# Probe_Schematic.net
KiCad netlist of a schematic drawn in EAGLE
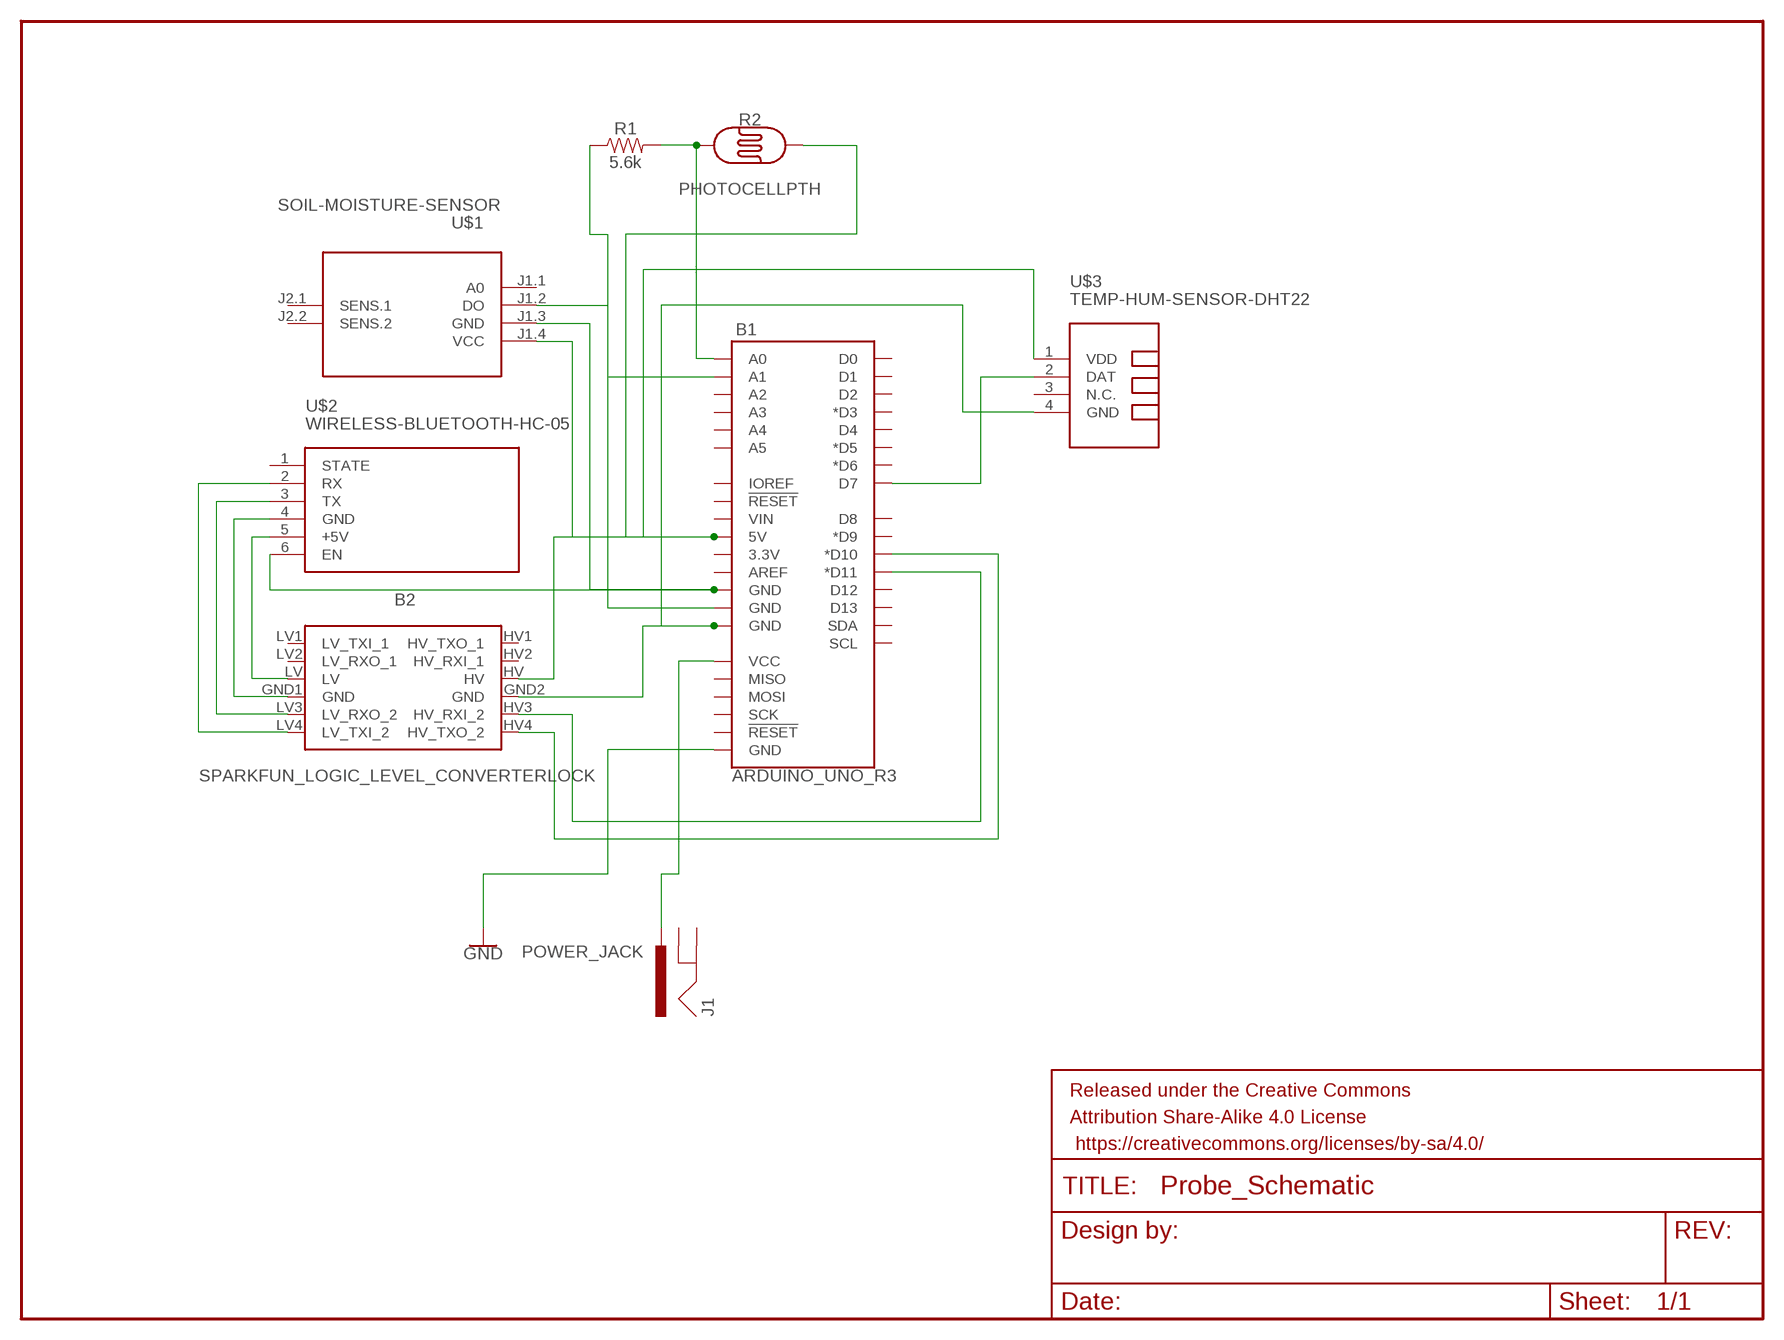
[diagram p0: schematic, sheet 1]

(export (version "E")
  (design (tool "Eeschema 10.0.6"))
  (components
    (comp (ref "B1")
      (value "ARDUINO_UNO_R3")
      (footprint "eagle-import:ARDUINO_R3")
      (libsource (lib "eagle-import") (part "ARDUINO_UNO_R3"))
    )
    (comp (ref "B2")
      (value "SPARKFUN_LOGIC_LEVEL_CONVERTERLOCK")
      (footprint "eagle-import:SPARKFUN_LOGIC_LEVEL_CONVERTER_LOCK")
      (libsource (lib "eagle-import") (part "SPARKFUN_LOGIC_LEVEL_CONVERTERLOCK"))
    )
    (comp (ref "FRAME1")
      (value "FRAME-LETTER")
      (footprint "eagle-import:CREATIVE_COMMONS")
      (libsource (lib "eagle-import") (part "FRAME-LETTER"))
    )
    (comp (ref "J1")
      (value "POWER_JACK")
      (footprint "eagle-import:POWER_JACK_PTH")
      (libsource (lib "eagle-import") (part "POWER_JACK"))
    )
    (comp (ref "R1")
      (value "5.6k")
      (footprint "eagle-import:0603")
      (libsource (lib "eagle-import") (part "5.6KOHM-0603-1/10W-1%"))
    )
    (comp (ref "R2")
      (value "PHOTOCELLPTH")
      (footprint "eagle-import:PHOTOCELL")
      (libsource (lib "eagle-import") (part "PHOTOCELLPTH"))
    )
    (comp (ref "U$1")
      (value "SOIL-MOISTURE-SENSOR")
      (footprint "eagle-import:SOIL-MOISTURE-SENSOR")
      (libsource (lib "eagle-import") (part "SOIL-MOISTURE-SENSOR"))
    )
    (comp (ref "U$2")
      (value "WIRELESS-BLUETOOTH-HC-05")
      (footprint "eagle-import:WIRELESS-BLUETOOTH-HC-05")
      (libsource (lib "eagle-import") (part "WIRELESS-BLUETOOTH-HC-05"))
    )
    (comp (ref "U$3")
      (value "TEMP-HUM-SENSOR-DHT22")
      (footprint "eagle-import:TEMP-HUM-SENSOR-DHT22")
      (libsource (lib "eagle-import") (part "TEMP-HUM-SENSOR-DHT22"))
    )
  )
  (nets
    (net (code "1") (name "GND") (class "Default")
      (node (ref "B1") (pin "GND@1") (pinfunction "GND_GND@1") (pintype "bidirectional"))
    )
    (net (code "2") (name "Net-(B1-*D10)") (class "Default")
      (node (ref "B1") (pin "D10") (pinfunction "*D10_D10") (pintype "bidirectional"))
      (node (ref "B2") (pin "HV4") (pinfunction "HV_TXO_2_HV4") (pintype "bidirectional"))
    )
    (net (code "3") (name "Net-(B1-*D11)") (class "Default")
      (node (ref "B1") (pin "D11") (pinfunction "*D11_D11") (pintype "bidirectional"))
      (node (ref "B2") (pin "HV3") (pinfunction "HV_RXI_2_HV3") (pintype "bidirectional"))
    )
    (net (code "4") (name "Net-(B1-GND-PadGND@3)") (class "Default")
      (node (ref "B1") (pin "GND@3") (pinfunction "GND_GND@3") (pintype "bidirectional"))
      (node (ref "R1") (pin "1") (pinfunction "1_1") (pintype "passive"))
    )
    (net (code "5") (name "Net-(B1-PadVCC)") (class "Default")
      (node (ref "B1") (pin "VCC") (pinfunction "VCC_VCC") (pintype "bidirectional"))
      (node (ref "J1") (pin "PWR") (pinfunction "PWR_PWR") (pintype "bidirectional"))
    )
    (net (code "6") (name "Net-(B2-LV_RXO_2)") (class "Default")
      (node (ref "B2") (pin "LV3") (pinfunction "LV_RXO_2_LV3") (pintype "bidirectional"))
      (node (ref "U$2") (pin "3") (pinfunction "TX_3") (pintype "bidirectional"))
    )
    (net (code "7") (name "Net-(B2-LV_TXI_2)") (class "Default")
      (node (ref "B2") (pin "LV4") (pinfunction "LV_TXI_2_LV4") (pintype "bidirectional"))
      (node (ref "U$2") (pin "2") (pinfunction "RX_2") (pintype "bidirectional"))
    )
    (net (code "8") (name "Net-(R2-P$1)") (class "Default")
      (node (ref "B1") (pin "A0") (pinfunction "A0_A0") (pintype "bidirectional"))
      (node (ref "R1") (pin "2") (pinfunction "2_2") (pintype "passive"))
      (node (ref "R2") (pin "1") (pinfunction "P$1_1") (pintype "bidirectional"))
    )
    (net (code "9") (name "Net-(R2-P$2)") (class "Default")
      (node (ref "B1") (pin "5V") (pinfunction "5V_5V") (pintype "bidirectional"))
      (node (ref "B2") (pin "HV") (pinfunction "HV_HV") (pintype "power_in"))
      (node (ref "R2") (pin "2") (pinfunction "P$2_2") (pintype "bidirectional"))
      (node (ref "U$1") (pin "J1.4") (pinfunction "VCC_J1.4") (pintype "power_in"))
      (node (ref "U$3") (pin "1") (pinfunction "VDD_1") (pintype "power_in"))
    )
    (net (code "10") (name "Net-(U$1-DO)") (class "Default")
      (node (ref "B1") (pin "A1") (pinfunction "A1_A1") (pintype "bidirectional"))
      (node (ref "U$1") (pin "J1.2") (pinfunction "DO_J1.2") (pintype "output"))
    )
    (net (code "11") (name "Net-(U$1-GND)") (class "Default")
      (node (ref "B1") (pin "GND@4") (pinfunction "GND_GND@4") (pintype "bidirectional"))
      (node (ref "U$1") (pin "J1.3") (pinfunction "GND_J1.3") (pintype "power_in"))
      (node (ref "U$2") (pin "6") (pinfunction "EN_6") (pintype "bidirectional"))
    )
    (net (code "12") (name "Net-(U$2-+5V)") (class "Default")
      (node (ref "B2") (pin "LV") (pinfunction "LV_LV") (pintype "power_in"))
      (node (ref "U$2") (pin "5") (pinfunction "+5V_5") (pintype "power_in"))
    )
    (net (code "13") (name "Net-(U$2-GND)") (class "Default")
      (node (ref "B2") (pin "GND1") (pinfunction "GND_GND1") (pintype "power_in"))
      (node (ref "U$2") (pin "4") (pinfunction "GND_4") (pintype "power_in"))
    )
    (net (code "14") (name "Net-(U$3-DAT)") (class "Default")
      (node (ref "B1") (pin "D7") (pinfunction "D7_D7") (pintype "bidirectional"))
      (node (ref "U$3") (pin "2") (pinfunction "DAT_2") (pintype "bidirectional"))
    )
    (net (code "15") (name "Net-(U$3-GND)") (class "Default")
      (node (ref "B1") (pin "GND@2") (pinfunction "GND_GND@2") (pintype "bidirectional"))
      (node (ref "B2") (pin "GND2") (pinfunction "GND_GND2") (pintype "power_in"))
      (node (ref "U$3") (pin "4") (pinfunction "GND_4") (pintype "power_in"))
    )
    (net (code "16") (name "unconnected-(B1-*D3-PadD3)") (class "Default")
      (node (ref "B1") (pin "D3") (pinfunction "*D3_D3") (pintype "bidirectional"))
    )
    (net (code "17") (name "unconnected-(B1-*D5-PadD5)") (class "Default")
      (node (ref "B1") (pin "D5") (pinfunction "*D5_D5") (pintype "bidirectional"))
    )
    (net (code "18") (name "unconnected-(B1-*D6-PadD6)") (class "Default")
      (node (ref "B1") (pin "D6") (pinfunction "*D6_D6") (pintype "bidirectional"))
    )
    (net (code "19") (name "unconnected-(B1-*D9-PadD9)") (class "Default")
      (node (ref "B1") (pin "D9") (pinfunction "*D9_D9") (pintype "bidirectional"))
    )
    (net (code "20") (name "unconnected-(B1-Pad3.3V)") (class "Default")
      (node (ref "B1") (pin "3.3V") (pinfunction "3.3V_3.3V") (pintype "bidirectional"))
    )
    (net (code "21") (name "unconnected-(B1-PadA2)") (class "Default")
      (node (ref "B1") (pin "A2") (pinfunction "A2_A2") (pintype "bidirectional"))
    )
    (net (code "22") (name "unconnected-(B1-PadA3)") (class "Default")
      (node (ref "B1") (pin "A3") (pinfunction "A3_A3") (pintype "bidirectional"))
    )
    (net (code "23") (name "unconnected-(B1-PadA4)") (class "Default")
      (node (ref "B1") (pin "A4") (pinfunction "A4_A4") (pintype "bidirectional"))
    )
    (net (code "24") (name "unconnected-(B1-PadA5)") (class "Default")
      (node (ref "B1") (pin "A5") (pinfunction "A5_A5") (pintype "bidirectional"))
    )
    (net (code "25") (name "unconnected-(B1-PadAREF)") (class "Default")
      (node (ref "B1") (pin "AREF") (pinfunction "AREF_AREF") (pintype "bidirectional"))
    )
    (net (code "26") (name "unconnected-(B1-PadD0)") (class "Default")
      (node (ref "B1") (pin "D0") (pinfunction "D0_D0") (pintype "bidirectional"))
    )
    (net (code "27") (name "unconnected-(B1-PadD1)") (class "Default")
      (node (ref "B1") (pin "D1") (pinfunction "D1_D1") (pintype "bidirectional"))
    )
    (net (code "28") (name "unconnected-(B1-PadD2)") (class "Default")
      (node (ref "B1") (pin "D2") (pinfunction "D2_D2") (pintype "bidirectional"))
    )
    (net (code "29") (name "unconnected-(B1-PadD4)") (class "Default")
      (node (ref "B1") (pin "D4") (pinfunction "D4_D4") (pintype "bidirectional"))
    )
    (net (code "30") (name "unconnected-(B1-PadD8)") (class "Default")
      (node (ref "B1") (pin "D8") (pinfunction "D8_D8") (pintype "bidirectional"))
    )
    (net (code "31") (name "unconnected-(B1-PadD12)") (class "Default")
      (node (ref "B1") (pin "D12") (pinfunction "D12_D12") (pintype "bidirectional"))
    )
    (net (code "32") (name "unconnected-(B1-PadD13)") (class "Default")
      (node (ref "B1") (pin "D13") (pinfunction "D13_D13") (pintype "bidirectional"))
    )
    (net (code "33") (name "unconnected-(B1-PadIOREF)") (class "Default")
      (node (ref "B1") (pin "IOREF") (pinfunction "IOREF_IOREF") (pintype "bidirectional"))
    )
    (net (code "34") (name "unconnected-(B1-PadMISO)") (class "Default")
      (node (ref "B1") (pin "MISO") (pinfunction "MISO_MISO") (pintype "bidirectional"))
    )
    (net (code "35") (name "unconnected-(B1-PadMOSI)") (class "Default")
      (node (ref "B1") (pin "MOSI") (pinfunction "MOSI_MOSI") (pintype "bidirectional"))
    )
    (net (code "36") (name "unconnected-(B1-PadSCK)") (class "Default")
      (node (ref "B1") (pin "SCK") (pinfunction "SCK_SCK") (pintype "bidirectional"))
    )
    (net (code "37") (name "unconnected-(B1-PadSCL)") (class "Default")
      (node (ref "B1") (pin "SCL") (pinfunction "SCL_SCL") (pintype "bidirectional"))
    )
    (net (code "38") (name "unconnected-(B1-PadSDA)") (class "Default")
      (node (ref "B1") (pin "SDA") (pinfunction "SDA_SDA") (pintype "bidirectional"))
    )
    (net (code "39") (name "unconnected-(B1-PadVIN)") (class "Default")
      (node (ref "B1") (pin "VIN") (pinfunction "VIN_VIN") (pintype "bidirectional"))
    )
    (net (code "40") (name "unconnected-(B1-~{RESET}-PadRESET@1)") (class "Default")
      (node (ref "B1") (pin "RESET@1") (pinfunction "~{RESET}_RESET@1") (pintype "bidirectional"))
    )
    (net (code "41") (name "unconnected-(B1-~{RESET}-PadRESET@2)") (class "Default")
      (node (ref "B1") (pin "RESET@2") (pinfunction "~{RESET}_RESET@2") (pintype "bidirectional"))
    )
    (net (code "42") (name "unconnected-(B2-HV_RXI_1-PadHV2)") (class "Default")
      (node (ref "B2") (pin "HV2") (pinfunction "HV_RXI_1_HV2") (pintype "bidirectional"))
    )
    (net (code "43") (name "unconnected-(B2-HV_TXO_1-PadHV1)") (class "Default")
      (node (ref "B2") (pin "HV1") (pinfunction "HV_TXO_1_HV1") (pintype "bidirectional"))
    )
    (net (code "44") (name "unconnected-(B2-LV_RXO_1-PadLV2)") (class "Default")
      (node (ref "B2") (pin "LV2") (pinfunction "LV_RXO_1_LV2") (pintype "bidirectional"))
    )
    (net (code "45") (name "unconnected-(B2-LV_TXI_1-PadLV1)") (class "Default")
      (node (ref "B2") (pin "LV1") (pinfunction "LV_TXI_1_LV1") (pintype "bidirectional"))
    )
    (net (code "46") (name "unconnected-(J1-PadGND)") (class "Default")
      (node (ref "J1") (pin "GND") (pinfunction "GND_GND") (pintype "bidirectional"))
    )
    (net (code "47") (name "unconnected-(J1-PadGNDBREAK)") (class "Default")
      (node (ref "J1") (pin "GNDBREAK") (pinfunction "GNDBREAK_GNDBREAK") (pintype "bidirectional"))
    )
    (net (code "48") (name "unconnected-(U$1-A0-PadJ1.1)") (class "Default")
      (node (ref "U$1") (pin "J1.1") (pinfunction "A0_J1.1") (pintype "bidirectional"))
    )
    (net (code "49") (name "unconnected-(U$1-SENS.1-PadJ2.1)") (class "Default")
      (node (ref "U$1") (pin "J2.1") (pinfunction "SENS.1_J2.1") (pintype "bidirectional"))
    )
    (net (code "50") (name "unconnected-(U$1-SENS.2-PadJ2.2)") (class "Default")
      (node (ref "U$1") (pin "J2.2") (pinfunction "SENS.2_J2.2") (pintype "bidirectional"))
    )
    (net (code "51") (name "unconnected-(U$2-STATE-Pad1)") (class "Default")
      (node (ref "U$2") (pin "1") (pinfunction "STATE_1") (pintype "bidirectional"))
    )
    (net (code "52") (name "unconnected-(U$3-N.C.-Pad3)") (class "Default")
      (node (ref "U$3") (pin "3") (pinfunction "N.C._3") (pintype "passive"))
    )
  )
)
